# logic_swerve.net
KiCad netlist of a schematic drawn in EAGLE
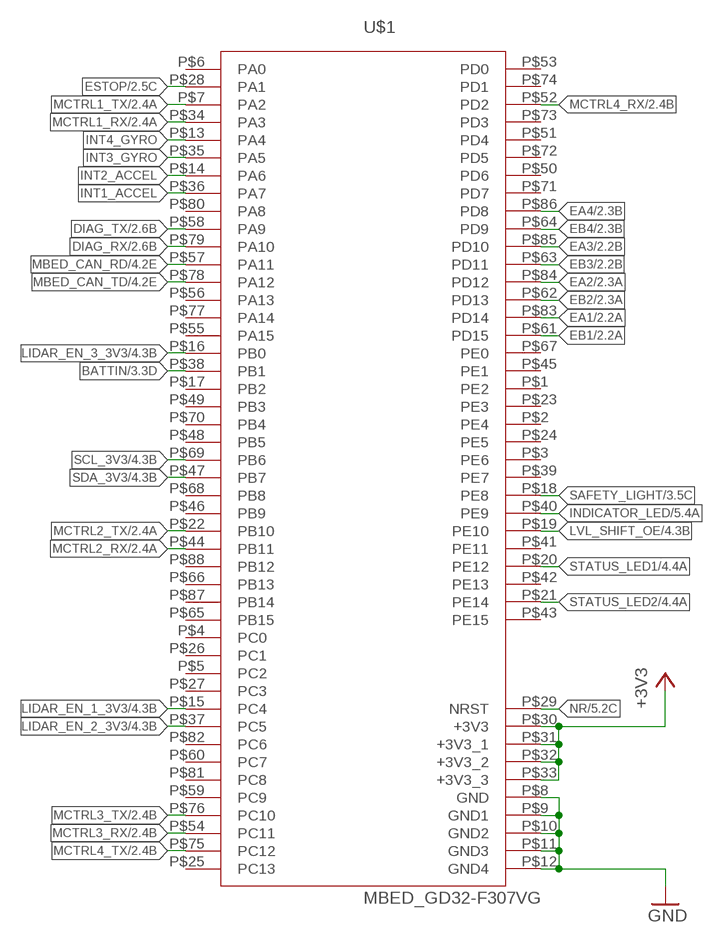
[diagram p0: schematic, sheet 1]
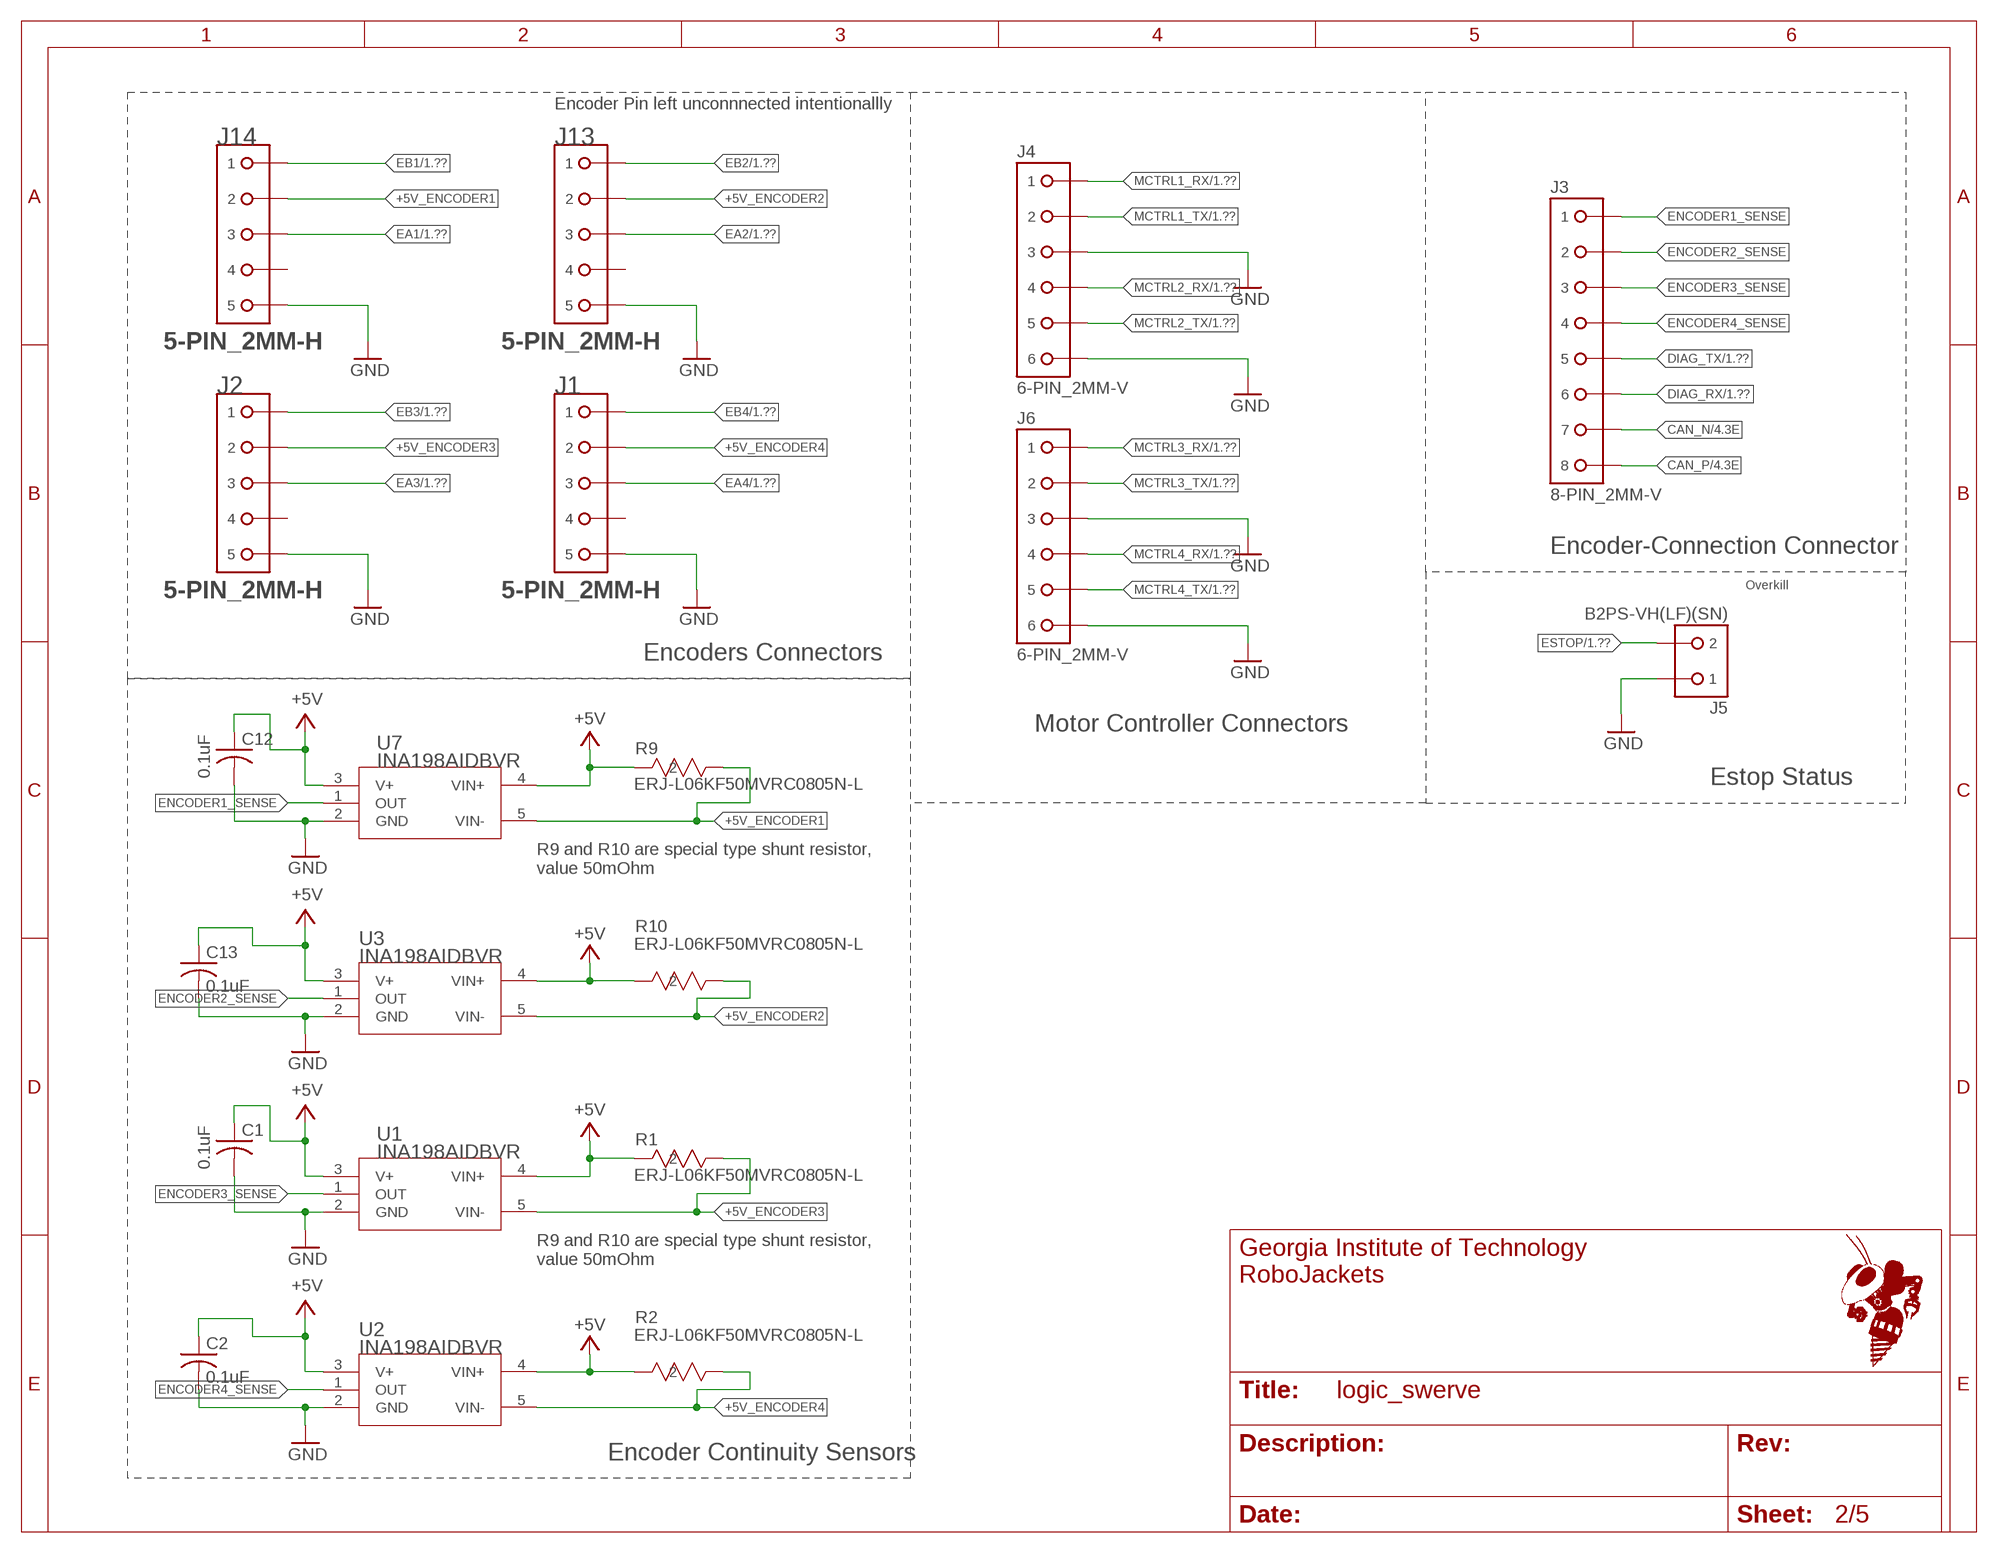
[diagram p1: schematic, sheet 2]
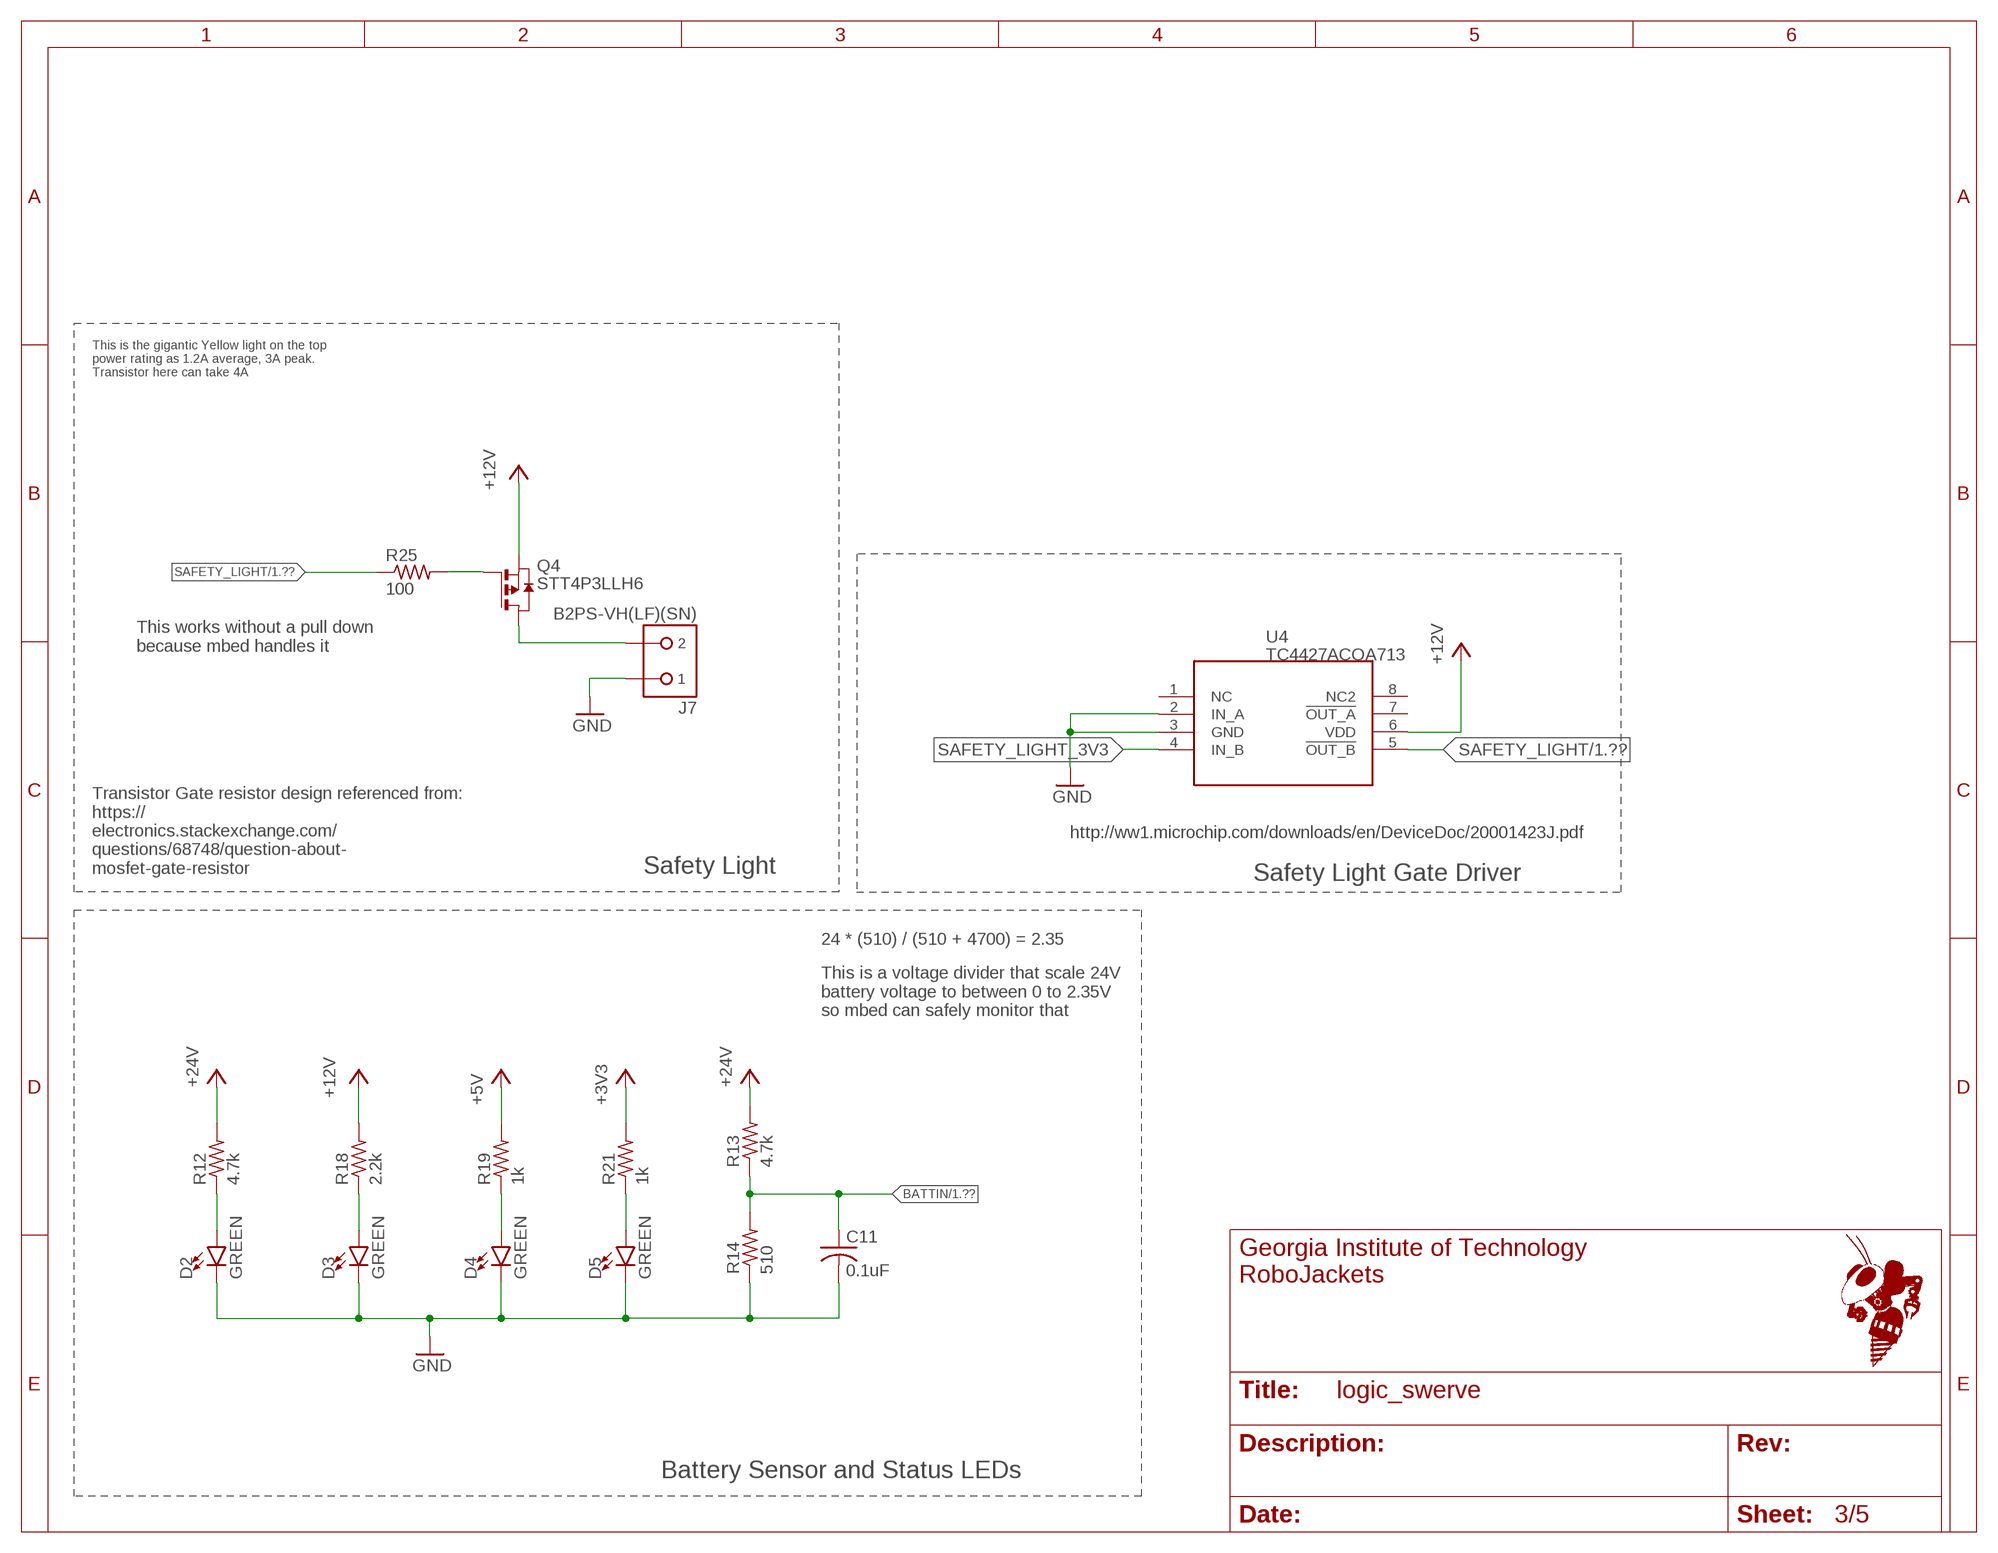
[diagram p2: schematic, sheet 3]
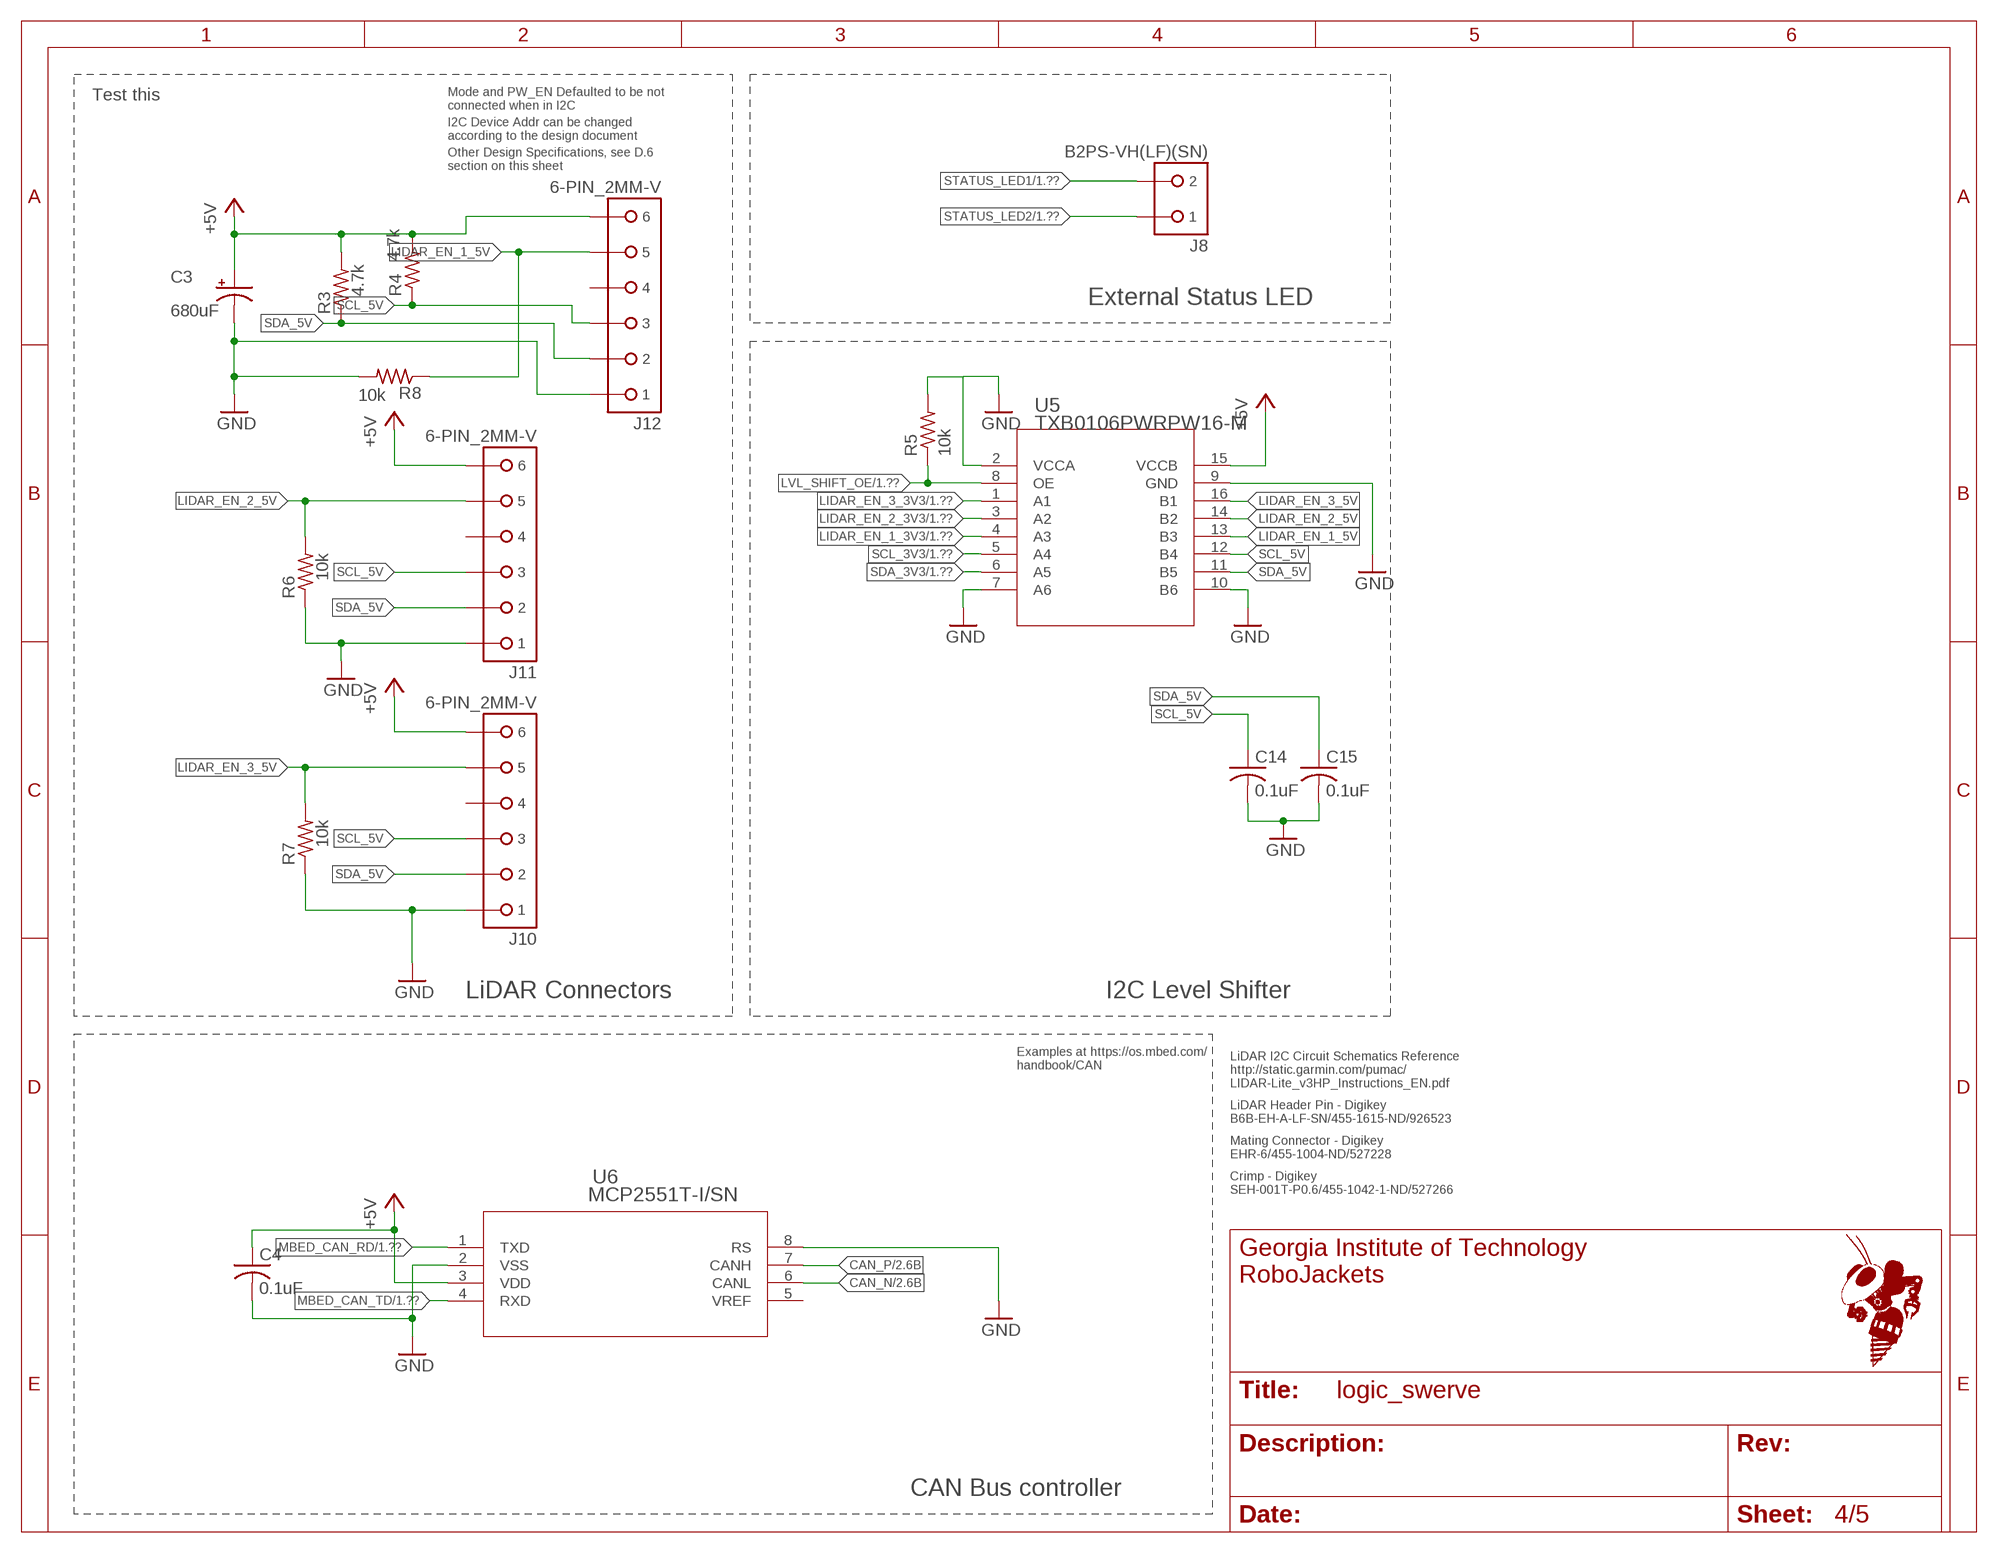
[diagram p3: schematic, sheet 4]
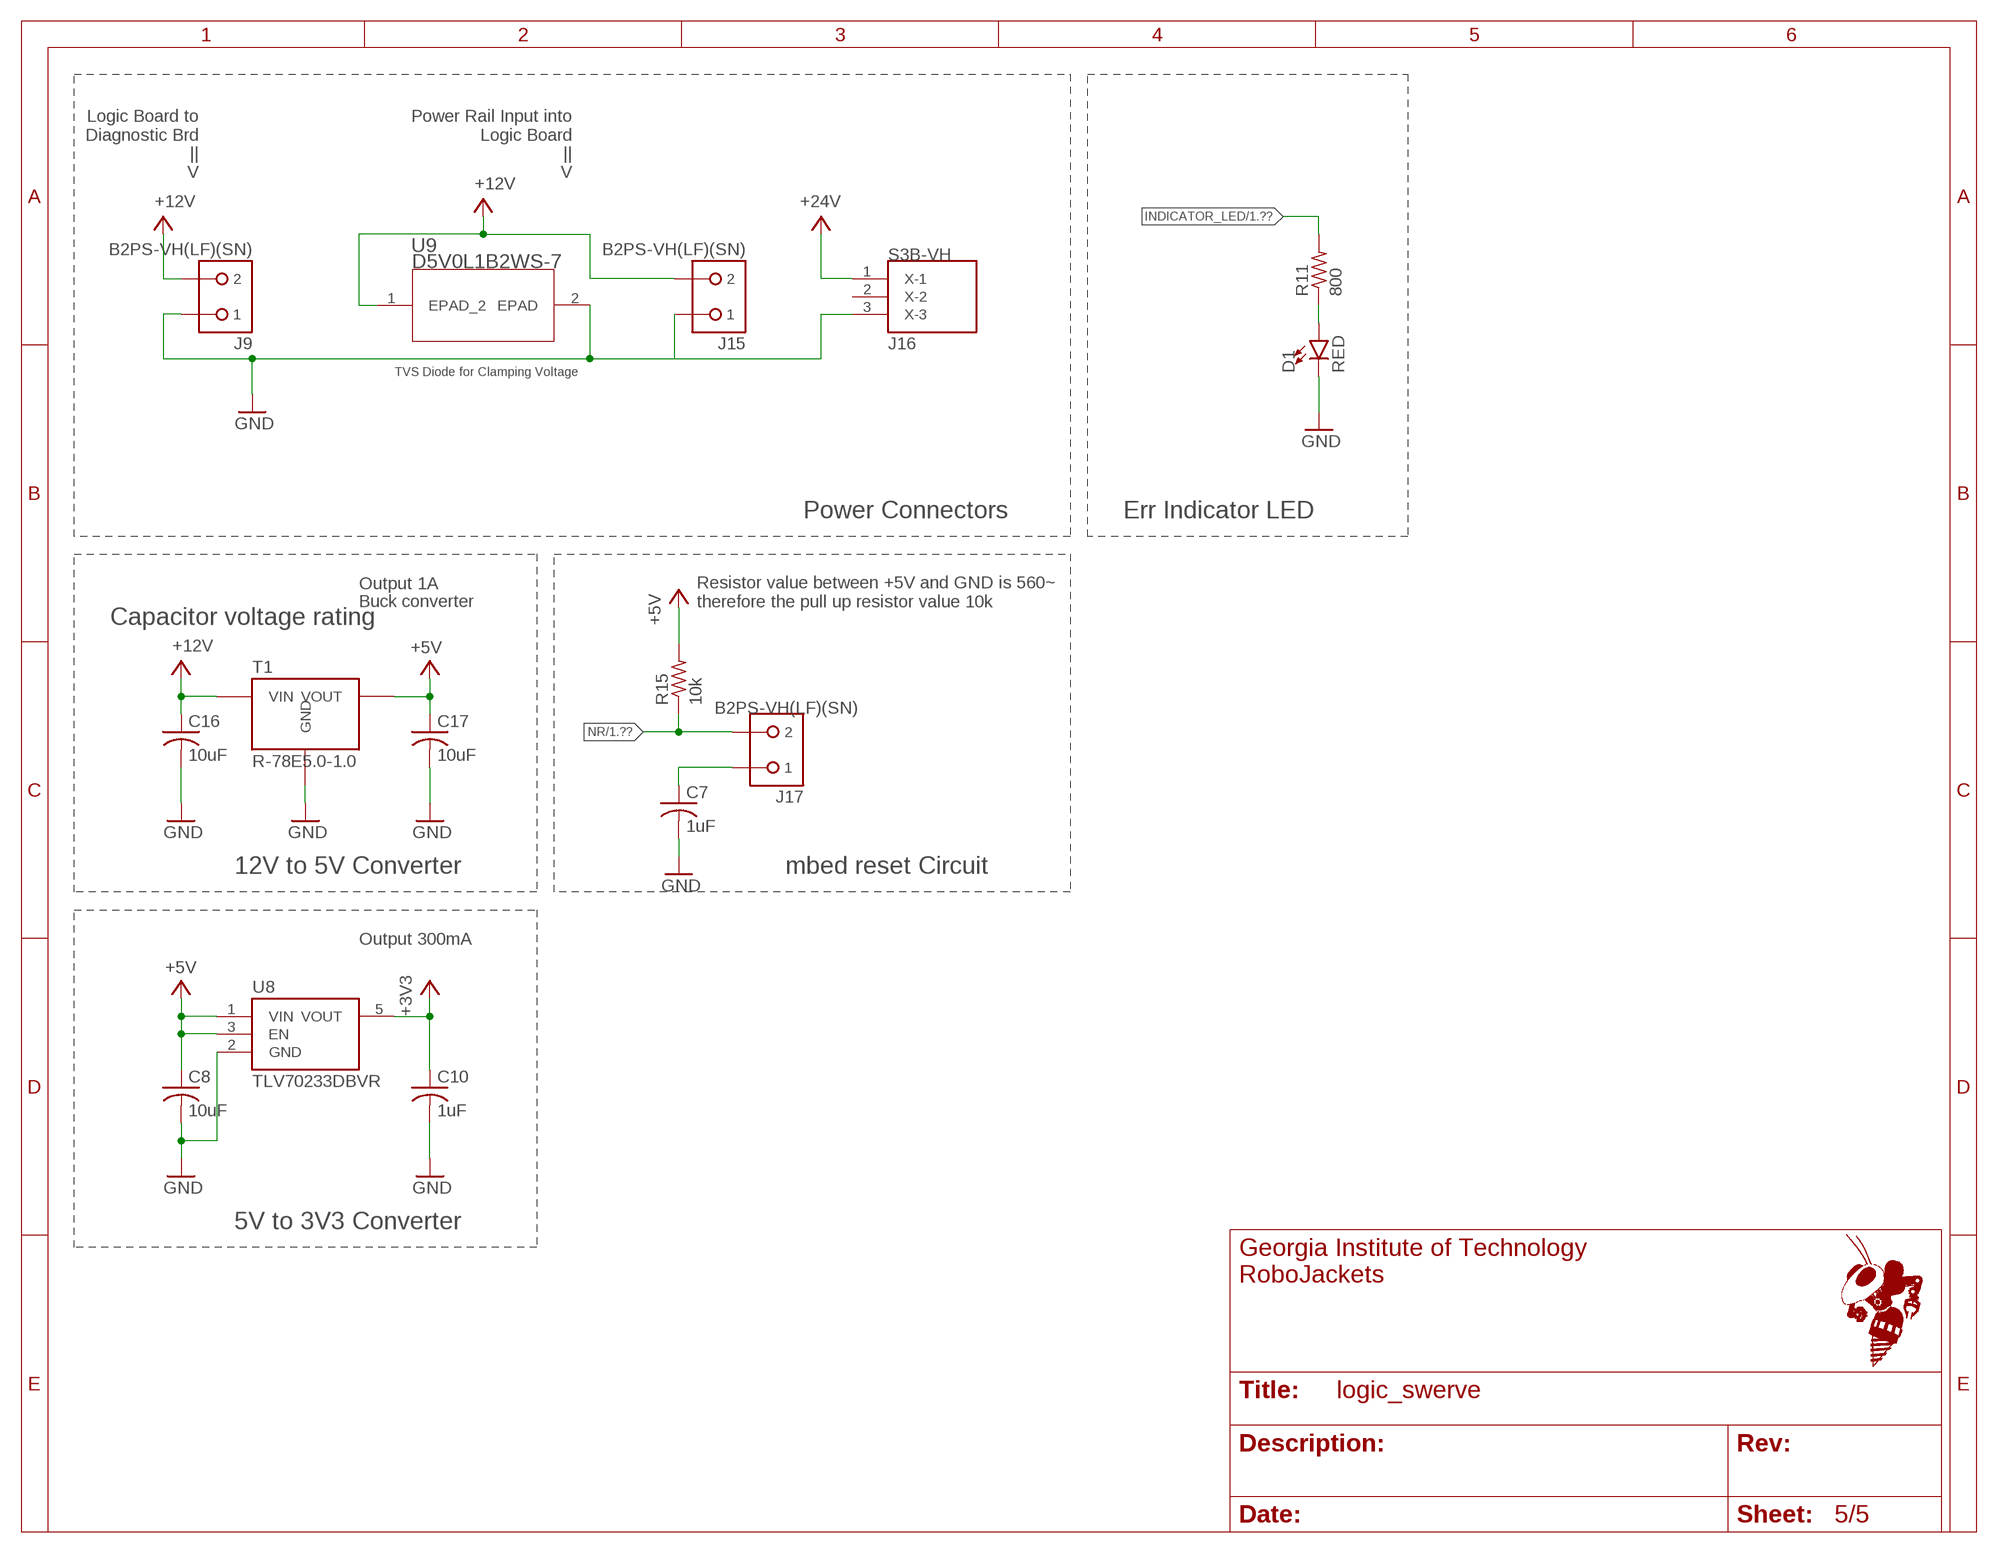
[diagram p4: schematic, sheet 5]

(export (version "E")
  (design (tool "Eeschema 10.0.6"))
  (components
    (comp (ref "C11")
      (value "0.1uF")
      (footprint "eagle-import:C0603")
      (libsource (lib "eagle-import") (part "C-USC0603"))
    )
    (comp (ref "D2")
      (value "GREEN")
      (footprint "eagle-import:LED-0603")
      (libsource (lib "eagle-import") (part "LED-BLUE0603"))
    )
    (comp (ref "D3")
      (value "GREEN")
      (footprint "eagle-import:LED-0603")
      (libsource (lib "eagle-import") (part "LED-BLUE0603"))
    )
    (comp (ref "D4")
      (value "GREEN")
      (footprint "eagle-import:LED-0603")
      (libsource (lib "eagle-import") (part "LED-GREEN0603"))
    )
    (comp (ref "D5")
      (value "GREEN")
      (footprint "eagle-import:LED-0603")
      (libsource (lib "eagle-import") (part "LED-GREEN0603"))
    )
    (comp (ref "J7")
      (value "B2PS-VH(LF)(SN)")
      (footprint "eagle-import:B2PS-CENTERED")
      (libsource (lib "eagle-import") (part "B2P?-VH(LF)(SN)S"))
    )
    (comp (ref "Q4")
      (value "STT4P3LLH6")
      (footprint "eagle-import:SOT23-6")
      (libsource (lib "eagle-import") (part "STT4P3LLH6"))
    )
    (comp (ref "R12")
      (value "4.7k")
      (footprint "eagle-import:R0603")
      (libsource (lib "eagle-import") (part "R-US_R0603"))
    )
    (comp (ref "R13")
      (value "4.7k")
      (footprint "eagle-import:R0603")
      (libsource (lib "eagle-import") (part "R-US_R0603"))
    )
    (comp (ref "R14")
      (value "510")
      (footprint "eagle-import:R0603")
      (libsource (lib "eagle-import") (part "R-US_R0603"))
    )
    (comp (ref "R18")
      (value "2.2k")
      (footprint "eagle-import:R0603")
      (libsource (lib "eagle-import") (part "R-US_R0603"))
    )
    (comp (ref "R19")
      (value "1k")
      (footprint "eagle-import:R0603")
      (libsource (lib "eagle-import") (part "R-US_R0603"))
    )
    (comp (ref "R21")
      (value "1k")
      (footprint "eagle-import:R0603")
      (libsource (lib "eagle-import") (part "R-US_R0603"))
    )
    (comp (ref "R25")
      (value "100")
      (footprint "eagle-import:R0603")
      (libsource (lib "eagle-import") (part "R-US_R0603"))
    )
    (comp (ref "U4")
      (value "TC4427ACOA713")
      (footprint "eagle-import:SOIC-8")
      (libsource (lib "eagle-import") (part "TC4427ACOA713"))
    )
    (comp (ref "U$1")
      (value "MBED_GD32-F307VG")
      (footprint "eagle-import:SWERVE_MBED")
      (libsource (lib "eagle-import") (part "MBED_GD32-F307VG"))
    )
    (comp (ref "C7")
      (value "1uF")
      (footprint "eagle-import:C0805")
      (libsource (lib "eagle-import") (part "C-USC0805"))
    )
    (comp (ref "C8")
      (value "10uF")
      (footprint "eagle-import:C0805")
      (libsource (lib "eagle-import") (part "C-USC0805"))
    )
    (comp (ref "C10")
      (value "1uF")
      (footprint "eagle-import:C0805")
      (libsource (lib "eagle-import") (part "C-USC0805"))
    )
    (comp (ref "C16")
      (value "10uF")
      (footprint "eagle-import:C0805")
      (libsource (lib "eagle-import") (part "C-USC0805"))
    )
    (comp (ref "C17")
      (value "10uF")
      (footprint "eagle-import:C0805")
      (libsource (lib "eagle-import") (part "C-USC0805"))
    )
    (comp (ref "D1")
      (value "RED")
      (footprint "eagle-import:LED-0603")
      (libsource (lib "eagle-import") (part "LED-BLUE0603"))
    )
    (comp (ref "J9")
      (value "B2PS-VH(LF)(SN)")
      (footprint "eagle-import:B2PS-CENTERED")
      (libsource (lib "eagle-import") (part "B2P?-VH(LF)(SN)S"))
    )
    (comp (ref "J15")
      (value "B2PS-VH(LF)(SN)")
      (footprint "eagle-import:B2PS-CENTERED")
      (libsource (lib "eagle-import") (part "B2P?-VH(LF)(SN)S"))
    )
    (comp (ref "J16")
      (value "S3B-VH")
      (footprint "eagle-import:S3B-VH")
      (libsource (lib "eagle-import") (part "S3B-VH"))
    )
    (comp (ref "J17")
      (value "B2PS-VH(LF)(SN)")
      (footprint "eagle-import:B2PS-CENTERED")
      (libsource (lib "eagle-import") (part "B2P?-VH(LF)(SN)S"))
    )
    (comp (ref "R11")
      (value "800")
      (footprint "eagle-import:R0603")
      (libsource (lib "eagle-import") (part "R-US_R0603"))
    )
    (comp (ref "R15")
      (value "10k")
      (footprint "eagle-import:R0603")
      (libsource (lib "eagle-import") (part "R-US_R0603"))
    )
    (comp (ref "T1")
      (value "R-78E5.0-1.0")
      (footprint "eagle-import:R-78E")
      (libsource (lib "eagle-import") (part "R-78E5.0-1.0"))
    )
    (comp (ref "U8")
      (value "TLV70233DBVR")
      (footprint "eagle-import:SOT-23-5")
      (libsource (lib "eagle-import") (part "TLV70233DBVR"))
    )
    (comp (ref "U9")
      (value "D5V0L1B2WS-7")
      (footprint "eagle-import:SOD323")
      (libsource (lib "eagle-import") (part "D5V0L1B2WS-7"))
    )
    (comp (ref "C3")
      (value "680uF")
      (footprint "eagle-import:E5-5")
      (libsource (lib "eagle-import") (part "CPOL-USE5-5"))
    )
    (comp (ref "C4")
      (value "0.1uF")
      (footprint "eagle-import:C0603")
      (libsource (lib "eagle-import") (part "C-USC0603"))
    )
    (comp (ref "C14")
      (value "0.1uF")
      (footprint "eagle-import:C0603")
      (libsource (lib "eagle-import") (part "C-USC0603"))
    )
    (comp (ref "C15")
      (value "0.1uF")
      (footprint "eagle-import:C0603")
      (libsource (lib "eagle-import") (part "C-USC0603"))
    )
    (comp (ref "J8")
      (value "B2PS-VH(LF)(SN)")
      (footprint "eagle-import:B2PS-CENTERED")
      (libsource (lib "eagle-import") (part "B2P?-VH(LF)(SN)S"))
    )
    (comp (ref "J10")
      (value "6-PIN_2MM-V")
      (footprint "eagle-import:2MM-6-V")
      (libsource (lib "eagle-import") (part "6-PIN_2MM-V"))
    )
    (comp (ref "J11")
      (value "6-PIN_2MM-V")
      (footprint "eagle-import:2MM-6-V")
      (libsource (lib "eagle-import") (part "6-PIN_2MM-V"))
    )
    (comp (ref "J12")
      (value "6-PIN_2MM-V")
      (footprint "eagle-import:2MM-6-V")
      (libsource (lib "eagle-import") (part "6-PIN_2MM-V"))
    )
    (comp (ref "R3")
      (value "4.7k")
      (footprint "eagle-import:R0603")
      (libsource (lib "eagle-import") (part "R-US_R0603"))
    )
    (comp (ref "R4")
      (value "4.7k")
      (footprint "eagle-import:R0603")
      (libsource (lib "eagle-import") (part "R-US_R0603"))
    )
    (comp (ref "R5")
      (value "10k")
      (footprint "eagle-import:R0603")
      (libsource (lib "eagle-import") (part "R-US_R0603"))
    )
    (comp (ref "R6")
      (value "10k")
      (footprint "eagle-import:R0603")
      (libsource (lib "eagle-import") (part "R-US_R0603"))
    )
    (comp (ref "R7")
      (value "10k")
      (footprint "eagle-import:R0603")
      (libsource (lib "eagle-import") (part "R-US_R0603"))
    )
    (comp (ref "R8")
      (value "10k")
      (footprint "eagle-import:R0603")
      (libsource (lib "eagle-import") (part "R-US_R0603"))
    )
    (comp (ref "U5")
      (value "TXB0106PWRPW16-M")
      (footprint "eagle-import:PW16-M")
      (fields (field (name "MANUFACTURER_PART_NUMBER") "TXB0106PWR"))
      (libsource (lib "eagle-import") (part "TXB0106PWRPW16-M"))
    )
    (comp (ref "U6")
      (value "MCP2551T-I/SN")
      (footprint "eagle-import:SOIC8-N_MC")
      (fields (field (name "MANUFACTURER_PART_NUMBER") "MCP2551TISN"))
      (libsource (lib "eagle-import") (part "MCP2551T-I/SN"))
    )
    (comp (ref "C1")
      (value "0.1uF")
      (footprint "eagle-import:C0603")
      (libsource (lib "eagle-import") (part "C-USC0603"))
    )
    (comp (ref "C2")
      (value "0.1uF")
      (footprint "eagle-import:C0603")
      (libsource (lib "eagle-import") (part "C-USC0603"))
    )
    (comp (ref "C12")
      (value "0.1uF")
      (footprint "eagle-import:C0603")
      (libsource (lib "eagle-import") (part "C-USC0603"))
    )
    (comp (ref "C13")
      (value "0.1uF")
      (footprint "eagle-import:C0603")
      (libsource (lib "eagle-import") (part "C-USC0603"))
    )
    (comp (ref "J1")
      (value "5-PIN_2MM-H")
      (footprint "eagle-import:2MM-5-H")
      (libsource (lib "eagle-import") (part "5-PIN_2MM-H"))
    )
    (comp (ref "J2")
      (value "5-PIN_2MM-H")
      (footprint "eagle-import:2MM-5-H")
      (libsource (lib "eagle-import") (part "5-PIN_2MM-H"))
    )
    (comp (ref "J3")
      (value "8-PIN_2MM-V")
      (footprint "eagle-import:2MM-8-V")
      (libsource (lib "eagle-import") (part "8-PIN_2MM-V"))
    )
    (comp (ref "J4")
      (value "6-PIN_2MM-V")
      (footprint "eagle-import:2MM-6-V")
      (libsource (lib "eagle-import") (part "6-PIN_2MM-V"))
    )
    (comp (ref "J5")
      (value "B2PS-VH(LF)(SN)")
      (footprint "eagle-import:B2PS-CENTERED")
      (libsource (lib "eagle-import") (part "B2P?-VH(LF)(SN)S"))
    )
    (comp (ref "J6")
      (value "6-PIN_2MM-V")
      (footprint "eagle-import:2MM-6-V")
      (libsource (lib "eagle-import") (part "6-PIN_2MM-V"))
    )
    (comp (ref "J13")
      (value "5-PIN_2MM-H")
      (footprint "eagle-import:2MM-5-H")
      (libsource (lib "eagle-import") (part "5-PIN_2MM-H"))
    )
    (comp (ref "J14")
      (value "5-PIN_2MM-H")
      (footprint "eagle-import:2MM-5-H")
      (libsource (lib "eagle-import") (part "5-PIN_2MM-H"))
    )
    (comp (ref "R1")
      (value "ERJ-L06KF50MVRC0805N-L")
      (footprint "eagle-import:RC0805N-L")
      (fields (field (name "MANUFACTURER_PART_NUMBER") "ERJL06KF50MV"))
      (libsource (lib "eagle-import") (part "ERJ-L06KF50MVRC0805N-L"))
    )
    (comp (ref "R2")
      (value "ERJ-L06KF50MVRC0805N-L")
      (footprint "eagle-import:RC0805N-L")
      (fields (field (name "MANUFACTURER_PART_NUMBER") "ERJL06KF50MV"))
      (libsource (lib "eagle-import") (part "ERJ-L06KF50MVRC0805N-L"))
    )
    (comp (ref "R9")
      (value "ERJ-L06KF50MVRC0805N-L")
      (footprint "eagle-import:RC0805N-L")
      (fields (field (name "MANUFACTURER_PART_NUMBER") "ERJL06KF50MV"))
      (libsource (lib "eagle-import") (part "ERJ-L06KF50MVRC0805N-L"))
    )
    (comp (ref "R10")
      (value "ERJ-L06KF50MVRC0805N-L")
      (footprint "eagle-import:RC0805N-L")
      (fields (field (name "MANUFACTURER_PART_NUMBER") "ERJL06KF50MV"))
      (libsource (lib "eagle-import") (part "ERJ-L06KF50MVRC0805N-L"))
    )
    (comp (ref "U1")
      (value "INA198AIDBVR")
      (footprint "eagle-import:DBV5")
      (libsource (lib "eagle-import") (part "INA198AIDBVR"))
    )
    (comp (ref "U2")
      (value "INA198AIDBVR")
      (footprint "eagle-import:DBV5")
      (libsource (lib "eagle-import") (part "INA198AIDBVR"))
    )
    (comp (ref "U3")
      (value "INA198AIDBVR")
      (footprint "eagle-import:DBV5")
      (libsource (lib "eagle-import") (part "INA198AIDBVR"))
    )
    (comp (ref "U7")
      (value "INA198AIDBVR")
      (footprint "eagle-import:DBV5")
      (libsource (lib "eagle-import") (part "INA198AIDBVR"))
    )
  )
  (nets
    (net (code "1") (name "+3V3") (class "Default")
      (node (ref "C10") (pin "1") (pinfunction "1_1") (pintype "passive"))
      (node (ref "R21") (pin "2") (pinfunction "2_2") (pintype "passive"))
      (node (ref "U$1") (pin "P$30") (pinfunction "+3V3_P$30") (pintype "bidirectional"))
      (node (ref "U$1") (pin "P$31") (pinfunction "+3V3_1_P$31") (pintype "bidirectional"))
      (node (ref "U$1") (pin "P$32") (pinfunction "+3V3_2_P$32") (pintype "bidirectional"))
      (node (ref "U$1") (pin "P$33") (pinfunction "+3V3_3_P$33") (pintype "bidirectional"))
      (node (ref "U8") (pin "5") (pinfunction "VOUT_5") (pintype "bidirectional"))
    )
    (net (code "2") (name "+5V") (class "Default")
      (node (ref "C1") (pin "1") (pinfunction "1_1") (pintype "passive"))
      (node (ref "C12") (pin "1") (pinfunction "1_1") (pintype "passive"))
      (node (ref "C13") (pin "1") (pinfunction "1_1") (pintype "passive"))
      (node (ref "C17") (pin "1") (pinfunction "1_1") (pintype "passive"))
      (node (ref "C2") (pin "1") (pinfunction "1_1") (pintype "passive"))
      (node (ref "C3") (pin "+") (pinfunction "+_+") (pintype "passive"))
      (node (ref "C4") (pin "1") (pinfunction "1_1") (pintype "passive"))
      (node (ref "C8") (pin "1") (pinfunction "1_1") (pintype "passive"))
      (node (ref "J10") (pin "6") (pinfunction "6_6") (pintype "passive"))
      (node (ref "J11") (pin "6") (pinfunction "6_6") (pintype "passive"))
      (node (ref "J12") (pin "6") (pinfunction "6_6") (pintype "passive"))
      (node (ref "R1") (pin "2") (pinfunction "2_2") (pintype "passive"))
      (node (ref "R10") (pin "2") (pinfunction "2_2") (pintype "passive"))
      (node (ref "R15") (pin "2") (pinfunction "2_2") (pintype "passive"))
      (node (ref "R19") (pin "2") (pinfunction "2_2") (pintype "passive"))
      (node (ref "R2") (pin "2") (pinfunction "2_2") (pintype "passive"))
      (node (ref "R3") (pin "2") (pinfunction "2_2") (pintype "passive"))
      (node (ref "R4") (pin "2") (pinfunction "2_2") (pintype "passive"))
      (node (ref "R9") (pin "2") (pinfunction "2_2") (pintype "passive"))
      (node (ref "T1") (pin "3") (pinfunction "VOUT_3") (pintype "bidirectional"))
      (node (ref "U1") (pin "3") (pinfunction "V+_3") (pintype "power_in"))
      (node (ref "U1") (pin "4") (pinfunction "VIN+_4") (pintype "input"))
      (node (ref "U2") (pin "3") (pinfunction "V+_3") (pintype "power_in"))
      (node (ref "U2") (pin "4") (pinfunction "VIN+_4") (pintype "input"))
      (node (ref "U3") (pin "3") (pinfunction "V+_3") (pintype "power_in"))
      (node (ref "U3") (pin "4") (pinfunction "VIN+_4") (pintype "input"))
      (node (ref "U5") (pin "15") (pinfunction "VCCB_15") (pintype "power_in"))
      (node (ref "U6") (pin "3") (pinfunction "VDD_3") (pintype "passive"))
      (node (ref "U7") (pin "3") (pinfunction "V+_3") (pintype "power_in"))
      (node (ref "U7") (pin "4") (pinfunction "VIN+_4") (pintype "input"))
      (node (ref "U8") (pin "1") (pinfunction "VIN_1") (pintype "bidirectional"))
      (node (ref "U8") (pin "3") (pinfunction "EN_3") (pintype "bidirectional"))
    )
    (net (code "3") (name "+5V_ENCODER1") (class "Default")
      (node (ref "J14") (pin "2") (pinfunction "2_2") (pintype "passive"))
      (node (ref "R9") (pin "1") (pinfunction "1_1") (pintype "passive"))
      (node (ref "U7") (pin "5") (pinfunction "VIN-_5") (pintype "input"))
    )
    (net (code "4") (name "+5V_ENCODER2") (class "Default")
      (node (ref "J13") (pin "2") (pinfunction "2_2") (pintype "passive"))
      (node (ref "R10") (pin "1") (pinfunction "1_1") (pintype "passive"))
      (node (ref "U3") (pin "5") (pinfunction "VIN-_5") (pintype "input"))
    )
    (net (code "5") (name "+5V_ENCODER3") (class "Default")
      (node (ref "J2") (pin "2") (pinfunction "2_2") (pintype "passive"))
      (node (ref "R1") (pin "1") (pinfunction "1_1") (pintype "passive"))
      (node (ref "U1") (pin "5") (pinfunction "VIN-_5") (pintype "input"))
    )
    (net (code "6") (name "+5V_ENCODER4") (class "Default")
      (node (ref "J1") (pin "2") (pinfunction "2_2") (pintype "passive"))
      (node (ref "R2") (pin "1") (pinfunction "1_1") (pintype "passive"))
      (node (ref "U2") (pin "5") (pinfunction "VIN-_5") (pintype "input"))
    )
    (net (code "7") (name "+12V") (class "Default")
      (node (ref "C16") (pin "1") (pinfunction "1_1") (pintype "passive"))
      (node (ref "J15") (pin "2") (pinfunction "2_2") (pintype "bidirectional"))
      (node (ref "J9") (pin "2") (pinfunction "2_2") (pintype "bidirectional"))
      (node (ref "Q4") (pin "4") (pinfunction "S_4") (pintype "passive"))
      (node (ref "R18") (pin "2") (pinfunction "2_2") (pintype "passive"))
      (node (ref "T1") (pin "1") (pinfunction "VIN_1") (pintype "bidirectional"))
      (node (ref "U4") (pin "6") (pinfunction "VDD_6") (pintype "bidirectional"))
      (node (ref "U9") (pin "1") (pinfunction "EPAD_2_1") (pintype "passive"))
    )
    (net (code "8") (name "+24V") (class "Default")
      (node (ref "J16") (pin "1") (pinfunction "X-1_1") (pintype "bidirectional"))
      (node (ref "R12") (pin "2") (pinfunction "2_2") (pintype "passive"))
      (node (ref "R13") (pin "2") (pinfunction "2_2") (pintype "passive"))
    )
    (net (code "9") (name "BATTIN") (class "Default")
      (node (ref "C11") (pin "1") (pinfunction "1_1") (pintype "passive"))
      (node (ref "R13") (pin "1") (pinfunction "1_1") (pintype "passive"))
      (node (ref "R14") (pin "2") (pinfunction "2_2") (pintype "passive"))
      (node (ref "U$1") (pin "P$38") (pinfunction "PB1_P$38") (pintype "bidirectional"))
    )
    (net (code "10") (name "CAN_N") (class "Default")
      (node (ref "J3") (pin "7") (pinfunction "7_7") (pintype "passive"))
      (node (ref "U6") (pin "6") (pinfunction "CANL_6") (pintype "passive"))
    )
    (net (code "11") (name "CAN_P") (class "Default")
      (node (ref "J3") (pin "8") (pinfunction "8_8") (pintype "passive"))
      (node (ref "U6") (pin "7") (pinfunction "CANH_7") (pintype "passive"))
    )
    (net (code "12") (name "DIAG_RX") (class "Default")
      (node (ref "J3") (pin "6") (pinfunction "6_6") (pintype "passive"))
      (node (ref "U$1") (pin "P$79") (pinfunction "PA10_P$79") (pintype "bidirectional"))
    )
    (net (code "13") (name "DIAG_TX") (class "Default")
      (node (ref "J3") (pin "5") (pinfunction "5_5") (pintype "passive"))
      (node (ref "U$1") (pin "P$58") (pinfunction "PA9_P$58") (pintype "bidirectional"))
    )
    (net (code "14") (name "EA1") (class "Default")
      (node (ref "J14") (pin "3") (pinfunction "3_3") (pintype "passive"))
      (node (ref "U$1") (pin "P$83") (pinfunction "PD14_P$83") (pintype "bidirectional"))
    )
    (net (code "15") (name "EA2") (class "Default")
      (node (ref "J13") (pin "3") (pinfunction "3_3") (pintype "passive"))
      (node (ref "U$1") (pin "P$84") (pinfunction "PD12_P$84") (pintype "bidirectional"))
    )
    (net (code "16") (name "EA3") (class "Default")
      (node (ref "J2") (pin "3") (pinfunction "3_3") (pintype "passive"))
      (node (ref "U$1") (pin "P$85") (pinfunction "PD10_P$85") (pintype "bidirectional"))
    )
    (net (code "17") (name "EA4") (class "Default")
      (node (ref "J1") (pin "3") (pinfunction "3_3") (pintype "passive"))
      (node (ref "U$1") (pin "P$86") (pinfunction "PD8_P$86") (pintype "bidirectional"))
    )
    (net (code "18") (name "EB1") (class "Default")
      (node (ref "J14") (pin "1") (pinfunction "1_1") (pintype "passive"))
      (node (ref "U$1") (pin "P$61") (pinfunction "PD15_P$61") (pintype "bidirectional"))
    )
    (net (code "19") (name "EB2") (class "Default")
      (node (ref "J13") (pin "1") (pinfunction "1_1") (pintype "passive"))
      (node (ref "U$1") (pin "P$62") (pinfunction "PD13_P$62") (pintype "bidirectional"))
    )
    (net (code "20") (name "EB3") (class "Default")
      (node (ref "J2") (pin "1") (pinfunction "1_1") (pintype "passive"))
      (node (ref "U$1") (pin "P$63") (pinfunction "PD11_P$63") (pintype "bidirectional"))
    )
    (net (code "21") (name "EB4") (class "Default")
      (node (ref "J1") (pin "1") (pinfunction "1_1") (pintype "passive"))
      (node (ref "U$1") (pin "P$64") (pinfunction "PD9_P$64") (pintype "bidirectional"))
    )
    (net (code "22") (name "ENCODER1_SENSE") (class "Default")
      (node (ref "J3") (pin "1") (pinfunction "1_1") (pintype "passive"))
      (node (ref "U7") (pin "1") (pinfunction "OUT_1") (pintype "output"))
    )
    (net (code "23") (name "ENCODER2_SENSE") (class "Default")
      (node (ref "J3") (pin "2") (pinfunction "2_2") (pintype "passive"))
      (node (ref "U3") (pin "1") (pinfunction "OUT_1") (pintype "output"))
    )
    (net (code "24") (name "ENCODER3_SENSE") (class "Default")
      (node (ref "J3") (pin "3") (pinfunction "3_3") (pintype "passive"))
      (node (ref "U1") (pin "1") (pinfunction "OUT_1") (pintype "output"))
    )
    (net (code "25") (name "ENCODER4_SENSE") (class "Default")
      (node (ref "J3") (pin "4") (pinfunction "4_4") (pintype "passive"))
      (node (ref "U2") (pin "1") (pinfunction "OUT_1") (pintype "output"))
    )
    (net (code "26") (name "ESTOP") (class "Default")
      (node (ref "J5") (pin "2") (pinfunction "2_2") (pintype "bidirectional"))
      (node (ref "U$1") (pin "P$28") (pinfunction "PA1_P$28") (pintype "bidirectional"))
    )
    (net (code "27") (name "GND") (class "Default")
      (node (ref "C1") (pin "2") (pinfunction "2_2") (pintype "passive"))
      (node (ref "C10") (pin "2") (pinfunction "2_2") (pintype "passive"))
      (node (ref "C11") (pin "2") (pinfunction "2_2") (pintype "passive"))
      (node (ref "C12") (pin "2") (pinfunction "2_2") (pintype "passive"))
      (node (ref "C13") (pin "2") (pinfunction "2_2") (pintype "passive"))
      (node (ref "C14") (pin "2") (pinfunction "2_2") (pintype "passive"))
      (node (ref "C15") (pin "2") (pinfunction "2_2") (pintype "passive"))
      (node (ref "C16") (pin "2") (pinfunction "2_2") (pintype "passive"))
      (node (ref "C17") (pin "2") (pinfunction "2_2") (pintype "passive"))
      (node (ref "C2") (pin "2") (pinfunction "2_2") (pintype "passive"))
      (node (ref "C3") (pin "-") (pinfunction "-_-") (pintype "passive"))
      (node (ref "C4") (pin "2") (pinfunction "2_2") (pintype "passive"))
      (node (ref "C7") (pin "2") (pinfunction "2_2") (pintype "passive"))
      (node (ref "C8") (pin "2") (pinfunction "2_2") (pintype "passive"))
      (node (ref "D1") (pin "C") (pinfunction "C_C") (pintype "passive"))
      (node (ref "D2") (pin "C") (pinfunction "C_C") (pintype "passive"))
      (node (ref "D3") (pin "C") (pinfunction "C_C") (pintype "passive"))
      (node (ref "D4") (pin "C") (pinfunction "C_C") (pintype "passive"))
      (node (ref "D5") (pin "C") (pinfunction "C_C") (pintype "passive"))
      (node (ref "J1") (pin "5") (pinfunction "5_5") (pintype "passive"))
      (node (ref "J10") (pin "1") (pinfunction "1_1") (pintype "passive"))
      (node (ref "J11") (pin "1") (pinfunction "1_1") (pintype "passive"))
      (node (ref "J12") (pin "1") (pinfunction "1_1") (pintype "passive"))
      (node (ref "J13") (pin "5") (pinfunction "5_5") (pintype "passive"))
      (node (ref "J14") (pin "5") (pinfunction "5_5") (pintype "passive"))
      (node (ref "J15") (pin "1") (pinfunction "1_1") (pintype "bidirectional"))
      (node (ref "J16") (pin "3") (pinfunction "X-3_3") (pintype "bidirectional"))
      (node (ref "J2") (pin "5") (pinfunction "5_5") (pintype "passive"))
      (node (ref "J4") (pin "3") (pinfunction "3_3") (pintype "passive"))
      (node (ref "J4") (pin "6") (pinfunction "6_6") (pintype "passive"))
      (node (ref "J5") (pin "1") (pinfunction "1_1") (pintype "bidirectional"))
      (node (ref "J6") (pin "3") (pinfunction "3_3") (pintype "passive"))
      (node (ref "J6") (pin "6") (pinfunction "6_6") (pintype "passive"))
      (node (ref "J7") (pin "1") (pinfunction "1_1") (pintype "bidirectional"))
      (node (ref "J9") (pin "1") (pinfunction "1_1") (pintype "bidirectional"))
      (node (ref "R14") (pin "1") (pinfunction "1_1") (pintype "passive"))
      (node (ref "R5") (pin "2") (pinfunction "2_2") (pintype "passive"))
      (node (ref "R6") (pin "1") (pinfunction "1_1") (pintype "passive"))
      (node (ref "R7") (pin "1") (pinfunction "1_1") (pintype "passive"))
      (node (ref "R8") (pin "2") (pinfunction "2_2") (pintype "passive"))
      (node (ref "T1") (pin "2") (pinfunction "GND_2") (pintype "bidirectional"))
      (node (ref "U$1") (pin "P$10") (pinfunction "GND2_P$10") (pintype "bidirectional"))
      (node (ref "U$1") (pin "P$11") (pinfunction "GND3_P$11") (pintype "bidirectional"))
      (node (ref "U$1") (pin "P$12") (pinfunction "GND4_P$12") (pintype "bidirectional"))
      (node (ref "U$1") (pin "P$8") (pinfunction "GND_P$8") (pintype "bidirectional"))
      (node (ref "U$1") (pin "P$9") (pinfunction "GND1_P$9") (pintype "bidirectional"))
      (node (ref "U1") (pin "2") (pinfunction "GND_2") (pintype "power_in"))
      (node (ref "U2") (pin "2") (pinfunction "GND_2") (pintype "power_in"))
      (node (ref "U3") (pin "2") (pinfunction "GND_2") (pintype "power_in"))
      (node (ref "U4") (pin "2") (pinfunction "IN_A_2") (pintype "bidirectional"))
      (node (ref "U4") (pin "3") (pinfunction "GND_3") (pintype "bidirectional"))
      (node (ref "U5") (pin "10") (pinfunction "B6_10") (pintype "bidirectional"))
      (node (ref "U5") (pin "2") (pinfunction "VCCA_2") (pintype "power_in"))
      (node (ref "U5") (pin "7") (pinfunction "A6_7") (pintype "bidirectional"))
      (node (ref "U5") (pin "9") (pinfunction "GND_9") (pintype "power_in"))
      (node (ref "U6") (pin "2") (pinfunction "VSS_2") (pintype "passive"))
      (node (ref "U6") (pin "8") (pinfunction "RS_8") (pintype "passive"))
      (node (ref "U7") (pin "2") (pinfunction "GND_2") (pintype "power_in"))
      (node (ref "U8") (pin "2") (pinfunction "GND_2") (pintype "bidirectional"))
      (node (ref "U9") (pin "2") (pinfunction "EPAD_2") (pintype "passive"))
    )
    (net (code "28") (name "INDICATOR_LED") (class "Default")
      (node (ref "R11") (pin "2") (pinfunction "2_2") (pintype "passive"))
      (node (ref "U$1") (pin "P$40") (pinfunction "PE9_P$40") (pintype "bidirectional"))
    )
    (net (code "29") (name "INT1_ACCEL") (class "Default")
      (node (ref "U$1") (pin "P$36") (pinfunction "PA7_P$36") (pintype "bidirectional"))
    )
    (net (code "30") (name "INT2_ACCEL") (class "Default")
      (node (ref "U$1") (pin "P$14") (pinfunction "PA6_P$14") (pintype "bidirectional"))
    )
    (net (code "31") (name "INT3_GYRO") (class "Default")
      (node (ref "U$1") (pin "P$35") (pinfunction "PA5_P$35") (pintype "bidirectional"))
    )
    (net (code "32") (name "INT4_GYRO") (class "Default")
      (node (ref "U$1") (pin "P$13") (pinfunction "PA4_P$13") (pintype "bidirectional"))
    )
    (net (code "33") (name "LIDAR_EN_1_3V3") (class "Default")
      (node (ref "U$1") (pin "P$15") (pinfunction "PC4_P$15") (pintype "bidirectional"))
      (node (ref "U5") (pin "4") (pinfunction "A3_4") (pintype "bidirectional"))
    )
    (net (code "34") (name "LIDAR_EN_1_5V") (class "Default")
      (node (ref "J12") (pin "5") (pinfunction "5_5") (pintype "passive"))
      (node (ref "R8") (pin "1") (pinfunction "1_1") (pintype "passive"))
      (node (ref "U5") (pin "13") (pinfunction "B3_13") (pintype "bidirectional"))
    )
    (net (code "35") (name "LIDAR_EN_2_3V3") (class "Default")
      (node (ref "U$1") (pin "P$37") (pinfunction "PC5_P$37") (pintype "bidirectional"))
      (node (ref "U5") (pin "3") (pinfunction "A2_3") (pintype "bidirectional"))
    )
    (net (code "36") (name "LIDAR_EN_2_5V") (class "Default")
      (node (ref "J11") (pin "5") (pinfunction "5_5") (pintype "passive"))
      (node (ref "R6") (pin "2") (pinfunction "2_2") (pintype "passive"))
      (node (ref "U5") (pin "14") (pinfunction "B2_14") (pintype "bidirectional"))
    )
    (net (code "37") (name "LIDAR_EN_3_3V3") (class "Default")
      (node (ref "U$1") (pin "P$16") (pinfunction "PB0_P$16") (pintype "bidirectional"))
      (node (ref "U5") (pin "1") (pinfunction "A1_1") (pintype "bidirectional"))
    )
    (net (code "38") (name "LIDAR_EN_3_5V") (class "Default")
      (node (ref "J10") (pin "5") (pinfunction "5_5") (pintype "passive"))
      (node (ref "R7") (pin "2") (pinfunction "2_2") (pintype "passive"))
      (node (ref "U5") (pin "16") (pinfunction "B1_16") (pintype "bidirectional"))
    )
    (net (code "39") (name "LVL_SHIFT_OE") (class "Default")
      (node (ref "R5") (pin "1") (pinfunction "1_1") (pintype "passive"))
      (node (ref "U$1") (pin "P$19") (pinfunction "PE10_P$19") (pintype "bidirectional"))
      (node (ref "U5") (pin "8") (pinfunction "OE_8") (pintype "output"))
    )
    (net (code "40") (name "MBED_CAN_RD") (class "Default")
      (node (ref "U$1") (pin "P$57") (pinfunction "PA11_P$57") (pintype "bidirectional"))
      (node (ref "U6") (pin "1") (pinfunction "TXD_1") (pintype "passive"))
    )
    (net (code "41") (name "MBED_CAN_TD") (class "Default")
      (node (ref "U$1") (pin "P$78") (pinfunction "PA12_P$78") (pintype "bidirectional"))
      (node (ref "U6") (pin "4") (pinfunction "RXD_4") (pintype "passive"))
    )
    (net (code "42") (name "MCTRL1_RX") (class "Default")
      (node (ref "J4") (pin "1") (pinfunction "1_1") (pintype "passive"))
      (node (ref "U$1") (pin "P$34") (pinfunction "PA3_P$34") (pintype "bidirectional"))
    )
    (net (code "43") (name "MCTRL1_TX") (class "Default")
      (node (ref "J4") (pin "2") (pinfunction "2_2") (pintype "passive"))
      (node (ref "U$1") (pin "P$7") (pinfunction "PA2_P$7") (pintype "bidirectional"))
    )
    (net (code "44") (name "MCTRL2_RX") (class "Default")
      (node (ref "J4") (pin "4") (pinfunction "4_4") (pintype "passive"))
      (node (ref "U$1") (pin "P$44") (pinfunction "PB11_P$44") (pintype "bidirectional"))
    )
    (net (code "45") (name "MCTRL2_TX") (class "Default")
      (node (ref "J4") (pin "5") (pinfunction "5_5") (pintype "passive"))
      (node (ref "U$1") (pin "P$22") (pinfunction "PB10_P$22") (pintype "bidirectional"))
    )
    (net (code "46") (name "MCTRL3_RX") (class "Default")
      (node (ref "J6") (pin "1") (pinfunction "1_1") (pintype "passive"))
      (node (ref "U$1") (pin "P$54") (pinfunction "PC11_P$54") (pintype "bidirectional"))
    )
    (net (code "47") (name "MCTRL3_TX") (class "Default")
      (node (ref "J6") (pin "2") (pinfunction "2_2") (pintype "passive"))
      (node (ref "U$1") (pin "P$76") (pinfunction "PC10_P$76") (pintype "bidirectional"))
    )
    (net (code "48") (name "MCTRL4_RX") (class "Default")
      (node (ref "J6") (pin "4") (pinfunction "4_4") (pintype "passive"))
      (node (ref "U$1") (pin "P$52") (pinfunction "PD2_P$52") (pintype "bidirectional"))
    )
    (net (code "49") (name "MCTRL4_TX") (class "Default")
      (node (ref "J6") (pin "5") (pinfunction "5_5") (pintype "passive"))
      (node (ref "U$1") (pin "P$75") (pinfunction "PC12_P$75") (pintype "bidirectional"))
    )
    (net (code "50") (name "NR") (class "Default")
      (node (ref "J17") (pin "2") (pinfunction "2_2") (pintype "bidirectional"))
      (node (ref "R15") (pin "1") (pinfunction "1_1") (pintype "passive"))
      (node (ref "U$1") (pin "P$29") (pinfunction "NRST_P$29") (pintype "bidirectional"))
    )
    (net (code "51") (name "Net-(C7-Pad1)") (class "Default")
      (node (ref "C7") (pin "1") (pinfunction "1_1") (pintype "passive"))
      (node (ref "J17") (pin "1") (pinfunction "1_1") (pintype "bidirectional"))
    )
    (net (code "52") (name "Net-(D1-PadA)") (class "Default")
      (node (ref "D1") (pin "A") (pinfunction "A_A") (pintype "passive"))
      (node (ref "R11") (pin "1") (pinfunction "1_1") (pintype "passive"))
    )
    (net (code "53") (name "Net-(D2-PadA)") (class "Default")
      (node (ref "D2") (pin "A") (pinfunction "A_A") (pintype "passive"))
      (node (ref "R12") (pin "1") (pinfunction "1_1") (pintype "passive"))
    )
    (net (code "54") (name "Net-(D3-PadA)") (class "Default")
      (node (ref "D3") (pin "A") (pinfunction "A_A") (pintype "passive"))
      (node (ref "R18") (pin "1") (pinfunction "1_1") (pintype "passive"))
    )
    (net (code "55") (name "Net-(D4-PadA)") (class "Default")
      (node (ref "D4") (pin "A") (pinfunction "A_A") (pintype "passive"))
      (node (ref "R19") (pin "1") (pinfunction "1_1") (pintype "passive"))
    )
    (net (code "56") (name "Net-(D5-PadA)") (class "Default")
      (node (ref "D5") (pin "A") (pinfunction "A_A") (pintype "passive"))
      (node (ref "R21") (pin "1") (pinfunction "1_1") (pintype "passive"))
    )
    (net (code "57") (name "Net-(J7-Pad2)") (class "Default")
      (node (ref "J7") (pin "2") (pinfunction "2_2") (pintype "bidirectional"))
      (node (ref "Q4") (pin "1") (pinfunction "D_1") (pintype "passive"))
      (node (ref "Q4") (pin "2") (pinfunction "D_2") (pintype "passive"))
      (node (ref "Q4") (pin "5") (pinfunction "D_5") (pintype "passive"))
      (node (ref "Q4") (pin "6") (pinfunction "D_6") (pintype "passive"))
    )
    (net (code "58") (name "Net-(Q4-G)") (class "Default")
      (node (ref "Q4") (pin "3") (pinfunction "G_3") (pintype "passive"))
      (node (ref "R25") (pin "2") (pinfunction "2_2") (pintype "passive"))
    )
    (net (code "59") (name "SAFETY_LIGHT") (class "Default")
      (node (ref "R25") (pin "1") (pinfunction "1_1") (pintype "passive"))
      (node (ref "U$1") (pin "P$18") (pinfunction "PE8_P$18") (pintype "bidirectional"))
      (node (ref "U4") (pin "5") (pinfunction "~{OUT_B}_5") (pintype "bidirectional"))
    )
    (net (code "60") (name "SAFETY_LIGHT_3V3") (class "Default")
      (node (ref "U4") (pin "4") (pinfunction "IN_B_4") (pintype "bidirectional"))
    )
    (net (code "61") (name "SCL_3V3") (class "Default")
      (node (ref "U$1") (pin "P$69") (pinfunction "PB6_P$69") (pintype "bidirectional"))
      (node (ref "U5") (pin "5") (pinfunction "A4_5") (pintype "bidirectional"))
    )
    (net (code "62") (name "SCL_5V") (class "Default")
      (node (ref "C14") (pin "1") (pinfunction "1_1") (pintype "passive"))
      (node (ref "J10") (pin "3") (pinfunction "3_3") (pintype "passive"))
      (node (ref "J11") (pin "3") (pinfunction "3_3") (pintype "passive"))
      (node (ref "J12") (pin "3") (pinfunction "3_3") (pintype "passive"))
      (node (ref "R4") (pin "1") (pinfunction "1_1") (pintype "passive"))
      (node (ref "U5") (pin "12") (pinfunction "B4_12") (pintype "bidirectional"))
    )
    (net (code "63") (name "SDA_3V3") (class "Default")
      (node (ref "U$1") (pin "P$47") (pinfunction "PB7_P$47") (pintype "bidirectional"))
      (node (ref "U5") (pin "6") (pinfunction "A5_6") (pintype "bidirectional"))
    )
    (net (code "64") (name "SDA_5V") (class "Default")
      (node (ref "C15") (pin "1") (pinfunction "1_1") (pintype "passive"))
      (node (ref "J10") (pin "2") (pinfunction "2_2") (pintype "passive"))
      (node (ref "J11") (pin "2") (pinfunction "2_2") (pintype "passive"))
      (node (ref "J12") (pin "2") (pinfunction "2_2") (pintype "passive"))
      (node (ref "R3") (pin "1") (pinfunction "1_1") (pintype "passive"))
      (node (ref "U5") (pin "11") (pinfunction "B5_11") (pintype "bidirectional"))
    )
    (net (code "65") (name "STATUS_LED1") (class "Default")
      (node (ref "J8") (pin "2") (pinfunction "2_2") (pintype "bidirectional"))
      (node (ref "U$1") (pin "P$20") (pinfunction "PE12_P$20") (pintype "bidirectional"))
    )
    (net (code "66") (name "STATUS_LED2") (class "Default")
      (node (ref "J8") (pin "1") (pinfunction "1_1") (pintype "bidirectional"))
      (node (ref "U$1") (pin "P$21") (pinfunction "PE14_P$21") (pintype "bidirectional"))
    )
    (net (code "67") (name "unconnected-(J1-Pad4)") (class "Default")
      (node (ref "J1") (pin "4") (pinfunction "4_4") (pintype "passive"))
    )
    (net (code "68") (name "unconnected-(J2-Pad4)") (class "Default")
      (node (ref "J2") (pin "4") (pinfunction "4_4") (pintype "passive"))
    )
    (net (code "69") (name "unconnected-(J10-Pad4)") (class "Default")
      (node (ref "J10") (pin "4") (pinfunction "4_4") (pintype "passive"))
    )
    (net (code "70") (name "unconnected-(J11-Pad4)") (class "Default")
      (node (ref "J11") (pin "4") (pinfunction "4_4") (pintype "passive"))
    )
    (net (code "71") (name "unconnected-(J12-Pad4)") (class "Default")
      (node (ref "J12") (pin "4") (pinfunction "4_4") (pintype "passive"))
    )
    (net (code "72") (name "unconnected-(J13-Pad4)") (class "Default")
      (node (ref "J13") (pin "4") (pinfunction "4_4") (pintype "passive"))
    )
    (net (code "73") (name "unconnected-(J14-Pad4)") (class "Default")
      (node (ref "J14") (pin "4") (pinfunction "4_4") (pintype "passive"))
    )
    (net (code "74") (name "unconnected-(J16-X-2-Pad2)") (class "Default")
      (node (ref "J16") (pin "2") (pinfunction "X-2_2") (pintype "bidirectional"))
    )
    (net (code "75") (name "unconnected-(U$1-PA0-PadP$6)") (class "Default")
      (node (ref "U$1") (pin "P$6") (pinfunction "PA0_P$6") (pintype "bidirectional"))
    )
    (net (code "76") (name "unconnected-(U$1-PA8-PadP$80)") (class "Default")
      (node (ref "U$1") (pin "P$80") (pinfunction "PA8_P$80") (pintype "bidirectional"))
    )
    (net (code "77") (name "unconnected-(U$1-PA13-PadP$56)") (class "Default")
      (node (ref "U$1") (pin "P$56") (pinfunction "PA13_P$56") (pintype "bidirectional"))
    )
    (net (code "78") (name "unconnected-(U$1-PA14-PadP$77)") (class "Default")
      (node (ref "U$1") (pin "P$77") (pinfunction "PA14_P$77") (pintype "bidirectional"))
    )
    (net (code "79") (name "unconnected-(U$1-PA15-PadP$55)") (class "Default")
      (node (ref "U$1") (pin "P$55") (pinfunction "PA15_P$55") (pintype "bidirectional"))
    )
    (net (code "80") (name "unconnected-(U$1-PB2-PadP$17)") (class "Default")
      (node (ref "U$1") (pin "P$17") (pinfunction "PB2_P$17") (pintype "bidirectional"))
    )
    (net (code "81") (name "unconnected-(U$1-PB3-PadP$49)") (class "Default")
      (node (ref "U$1") (pin "P$49") (pinfunction "PB3_P$49") (pintype "bidirectional"))
    )
    (net (code "82") (name "unconnected-(U$1-PB4-PadP$70)") (class "Default")
      (node (ref "U$1") (pin "P$70") (pinfunction "PB4_P$70") (pintype "bidirectional"))
    )
    (net (code "83") (name "unconnected-(U$1-PB5-PadP$48)") (class "Default")
      (node (ref "U$1") (pin "P$48") (pinfunction "PB5_P$48") (pintype "bidirectional"))
    )
    (net (code "84") (name "unconnected-(U$1-PB8-PadP$68)") (class "Default")
      (node (ref "U$1") (pin "P$68") (pinfunction "PB8_P$68") (pintype "bidirectional"))
    )
    (net (code "85") (name "unconnected-(U$1-PB9-PadP$46)") (class "Default")
      (node (ref "U$1") (pin "P$46") (pinfunction "PB9_P$46") (pintype "bidirectional"))
    )
    (net (code "86") (name "unconnected-(U$1-PB12-PadP$88)") (class "Default")
      (node (ref "U$1") (pin "P$88") (pinfunction "PB12_P$88") (pintype "bidirectional"))
    )
    (net (code "87") (name "unconnected-(U$1-PB13-PadP$66)") (class "Default")
      (node (ref "U$1") (pin "P$66") (pinfunction "PB13_P$66") (pintype "bidirectional"))
    )
    (net (code "88") (name "unconnected-(U$1-PB14-PadP$87)") (class "Default")
      (node (ref "U$1") (pin "P$87") (pinfunction "PB14_P$87") (pintype "bidirectional"))
    )
    (net (code "89") (name "unconnected-(U$1-PB15-PadP$65)") (class "Default")
      (node (ref "U$1") (pin "P$65") (pinfunction "PB15_P$65") (pintype "bidirectional"))
    )
    (net (code "90") (name "unconnected-(U$1-PC0-PadP$4)") (class "Default")
      (node (ref "U$1") (pin "P$4") (pinfunction "PC0_P$4") (pintype "bidirectional"))
    )
    (net (code "91") (name "unconnected-(U$1-PC1-PadP$26)") (class "Default")
      (node (ref "U$1") (pin "P$26") (pinfunction "PC1_P$26") (pintype "bidirectional"))
    )
    (net (code "92") (name "unconnected-(U$1-PC2-PadP$5)") (class "Default")
      (node (ref "U$1") (pin "P$5") (pinfunction "PC2_P$5") (pintype "bidirectional"))
    )
    (net (code "93") (name "unconnected-(U$1-PC3-PadP$27)") (class "Default")
      (node (ref "U$1") (pin "P$27") (pinfunction "PC3_P$27") (pintype "bidirectional"))
    )
    (net (code "94") (name "unconnected-(U$1-PC6-PadP$82)") (class "Default")
      (node (ref "U$1") (pin "P$82") (pinfunction "PC6_P$82") (pintype "bidirectional"))
    )
    (net (code "95") (name "unconnected-(U$1-PC7-PadP$60)") (class "Default")
      (node (ref "U$1") (pin "P$60") (pinfunction "PC7_P$60") (pintype "bidirectional"))
    )
    (net (code "96") (name "unconnected-(U$1-PC8-PadP$81)") (class "Default")
      (node (ref "U$1") (pin "P$81") (pinfunction "PC8_P$81") (pintype "bidirectional"))
    )
    (net (code "97") (name "unconnected-(U$1-PC9-PadP$59)") (class "Default")
      (node (ref "U$1") (pin "P$59") (pinfunction "PC9_P$59") (pintype "bidirectional"))
    )
    (net (code "98") (name "unconnected-(U$1-PC13-PadP$25)") (class "Default")
      (node (ref "U$1") (pin "P$25") (pinfunction "PC13_P$25") (pintype "bidirectional"))
    )
    (net (code "99") (name "unconnected-(U$1-PD0-PadP$53)") (class "Default")
      (node (ref "U$1") (pin "P$53") (pinfunction "PD0_P$53") (pintype "bidirectional"))
    )
    (net (code "100") (name "unconnected-(U$1-PD1-PadP$74)") (class "Default")
      (node (ref "U$1") (pin "P$74") (pinfunction "PD1_P$74") (pintype "bidirectional"))
    )
    (net (code "101") (name "unconnected-(U$1-PD3-PadP$73)") (class "Default")
      (node (ref "U$1") (pin "P$73") (pinfunction "PD3_P$73") (pintype "bidirectional"))
    )
    (net (code "102") (name "unconnected-(U$1-PD4-PadP$51)") (class "Default")
      (node (ref "U$1") (pin "P$51") (pinfunction "PD4_P$51") (pintype "bidirectional"))
    )
    (net (code "103") (name "unconnected-(U$1-PD5-PadP$72)") (class "Default")
      (node (ref "U$1") (pin "P$72") (pinfunction "PD5_P$72") (pintype "bidirectional"))
    )
    (net (code "104") (name "unconnected-(U$1-PD6-PadP$50)") (class "Default")
      (node (ref "U$1") (pin "P$50") (pinfunction "PD6_P$50") (pintype "bidirectional"))
    )
    (net (code "105") (name "unconnected-(U$1-PD7-PadP$71)") (class "Default")
      (node (ref "U$1") (pin "P$71") (pinfunction "PD7_P$71") (pintype "bidirectional"))
    )
    (net (code "106") (name "unconnected-(U$1-PE0-PadP$67)") (class "Default")
      (node (ref "U$1") (pin "P$67") (pinfunction "PE0_P$67") (pintype "bidirectional"))
    )
    (net (code "107") (name "unconnected-(U$1-PE1-PadP$45)") (class "Default")
      (node (ref "U$1") (pin "P$45") (pinfunction "PE1_P$45") (pintype "bidirectional"))
    )
    (net (code "108") (name "unconnected-(U$1-PE2-PadP$1)") (class "Default")
      (node (ref "U$1") (pin "P$1") (pinfunction "PE2_P$1") (pintype "bidirectional"))
    )
    (net (code "109") (name "unconnected-(U$1-PE3-PadP$23)") (class "Default")
      (node (ref "U$1") (pin "P$23") (pinfunction "PE3_P$23") (pintype "bidirectional"))
    )
    (net (code "110") (name "unconnected-(U$1-PE4-PadP$2)") (class "Default")
      (node (ref "U$1") (pin "P$2") (pinfunction "PE4_P$2") (pintype "bidirectional"))
    )
    (net (code "111") (name "unconnected-(U$1-PE5-PadP$24)") (class "Default")
      (node (ref "U$1") (pin "P$24") (pinfunction "PE5_P$24") (pintype "bidirectional"))
    )
    (net (code "112") (name "unconnected-(U$1-PE6-PadP$3)") (class "Default")
      (node (ref "U$1") (pin "P$3") (pinfunction "PE6_P$3") (pintype "bidirectional"))
    )
    (net (code "113") (name "unconnected-(U$1-PE7-PadP$39)") (class "Default")
      (node (ref "U$1") (pin "P$39") (pinfunction "PE7_P$39") (pintype "bidirectional"))
    )
    (net (code "114") (name "unconnected-(U$1-PE11-PadP$41)") (class "Default")
      (node (ref "U$1") (pin "P$41") (pinfunction "PE11_P$41") (pintype "bidirectional"))
    )
    (net (code "115") (name "unconnected-(U$1-PE13-PadP$42)") (class "Default")
      (node (ref "U$1") (pin "P$42") (pinfunction "PE13_P$42") (pintype "bidirectional"))
    )
    (net (code "116") (name "unconnected-(U$1-PE15-PadP$43)") (class "Default")
      (node (ref "U$1") (pin "P$43") (pinfunction "PE15_P$43") (pintype "bidirectional"))
    )
    (net (code "117") (name "unconnected-(U4-NC-Pad1)") (class "Default")
      (node (ref "U4") (pin "1") (pinfunction "NC_1") (pintype "bidirectional"))
    )
    (net (code "118") (name "unconnected-(U4-NC2-Pad8)") (class "Default")
      (node (ref "U4") (pin "8") (pinfunction "NC2_8") (pintype "bidirectional"))
    )
    (net (code "119") (name "unconnected-(U4-~{OUT_A}-Pad7)") (class "Default")
      (node (ref "U4") (pin "7") (pinfunction "~{OUT_A}_7") (pintype "bidirectional"))
    )
    (net (code "120") (name "unconnected-(U6-VREF-Pad5)") (class "Default")
      (node (ref "U6") (pin "5") (pinfunction "VREF_5") (pintype "passive"))
    )
  )
)
